# Falhaber_sensors.net
KiCad netlist of a schematic drawn in EAGLE
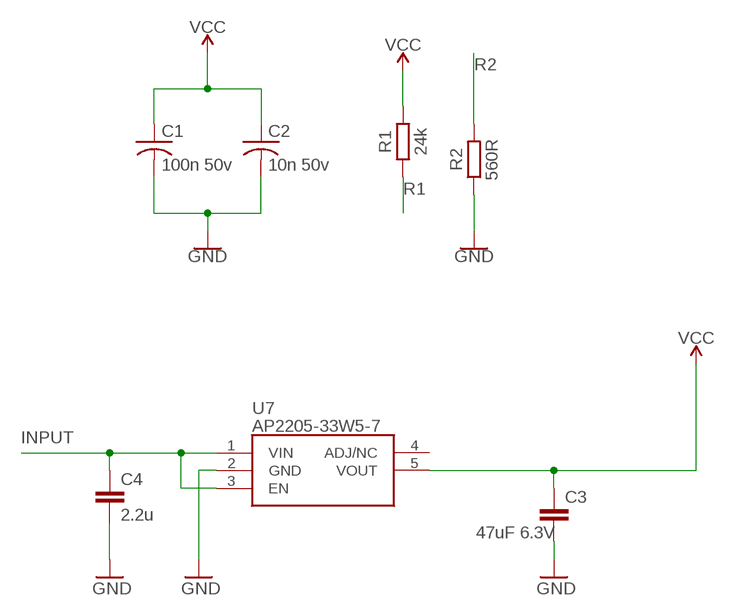
[diagram p0: schematic, sheet 1]

(export (version "E")
  (design (tool "Eeschema 10.0.6"))
  (components
    (comp (ref "C1")
      (value "100n 50v")
      (footprint "eagle-import:C0805")
      (libsource (lib "eagle-import") (part "C-USC0805"))
    )
    (comp (ref "C2")
      (value "10n 50v")
      (footprint "eagle-import:C0805")
      (libsource (lib "eagle-import") (part "C-USC0805"))
    )
    (comp (ref "C3")
      (value "47uF 6.3V")
      (footprint "eagle-import:0603-CAP")
      (libsource (lib "eagle-import") (part "4.7UF-6.3V-10%(0603)0603"))
    )
    (comp (ref "C4")
      (value "2.2u")
      (footprint "eagle-import:0603-CAP")
      (libsource (lib "eagle-import") (part "4.7UF-6.3V-10%(0603)0603"))
    )
    (comp (ref "R1")
      (value "24k")
      (footprint "eagle-import:RESC2012X65")
      (libsource (lib "eagle-import") (part "RCHIP-0805(2012-METRIC)_"))
    )
    (comp (ref "R2")
      (value "560R")
      (footprint "eagle-import:RESC2012X65")
      (libsource (lib "eagle-import") (part "RCHIP-0805(2012-METRIC)_"))
    )
    (comp (ref "U7")
      (value "AP2205-33W5-7")
      (footprint "eagle-import:SOT95P282X145-5N")
      (fields
        (field (name "MANUFACTURER_PART_NUMBER") "AP2205-W5-7")
        (field (name "MOUSER_PART_NUMBER") "621-AP2205-W5-7")
      )
      (libsource (lib "eagle-import") (part "AP2205-W5-7"))
    )
  )
  (nets
    (net (code "1") (name "/INPUT") (class "Default")
      (node (ref "C4") (pin "1") (pinfunction "1_1") (pintype "passive"))
      (node (ref "U7") (pin "1") (pinfunction "VIN_1") (pintype "bidirectional"))
      (node (ref "U7") (pin "3") (pinfunction "EN_3") (pintype "bidirectional"))
    )
    (net (code "2") (name "/R1") (class "Default")
      (node (ref "R1") (pin "1") (pinfunction "1_1") (pintype "passive"))
    )
    (net (code "3") (name "/R2") (class "Default")
      (node (ref "R2") (pin "2") (pinfunction "2_2") (pintype "passive"))
    )
    (net (code "4") (name "GND") (class "Default")
      (node (ref "C1") (pin "2") (pinfunction "2_2") (pintype "passive"))
      (node (ref "C2") (pin "2") (pinfunction "2_2") (pintype "passive"))
      (node (ref "C3") (pin "2") (pinfunction "2_2") (pintype "passive"))
      (node (ref "C4") (pin "2") (pinfunction "2_2") (pintype "passive"))
      (node (ref "R2") (pin "1") (pinfunction "1_1") (pintype "passive"))
      (node (ref "U7") (pin "2") (pinfunction "GND_2") (pintype "bidirectional"))
    )
    (net (code "5") (name "VCC") (class "Default")
      (node (ref "C1") (pin "1") (pinfunction "1_1") (pintype "passive"))
      (node (ref "C2") (pin "1") (pinfunction "1_1") (pintype "passive"))
      (node (ref "C3") (pin "1") (pinfunction "1_1") (pintype "passive"))
      (node (ref "R1") (pin "2") (pinfunction "2_2") (pintype "passive"))
      (node (ref "U7") (pin "5") (pinfunction "VOUT_5") (pintype "bidirectional"))
    )
    (net (code "6") (name "unconnected-(U7-ADJ{slash}NC-Pad4)") (class "Default")
      (node (ref "U7") (pin "4") (pinfunction "ADJ/NC_4") (pintype "bidirectional"))
    )
  )
)
